# tweeq-eMod_Splitter_UART.net
KiCad netlist of a schematic drawn in EAGLE
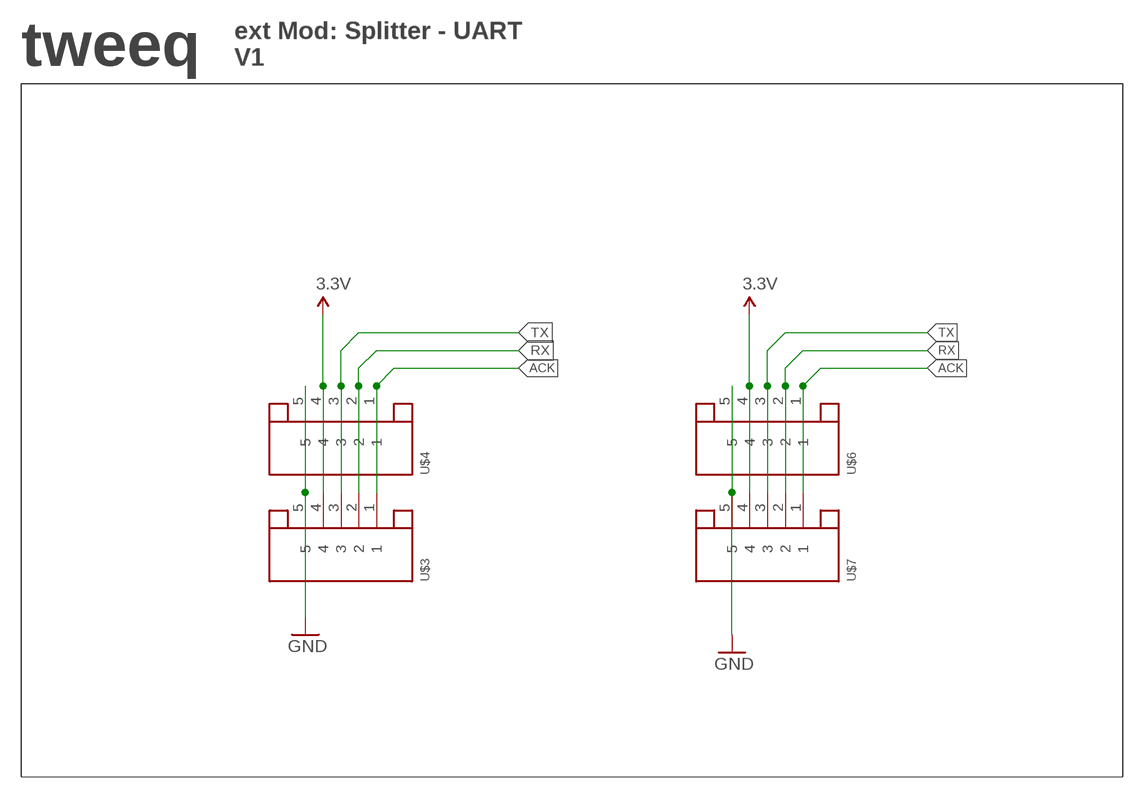
[diagram p0: schematic, sheet 1]

(export (version "E")
  (design (tool "Eeschema 10.0.6"))
  (components
    (comp (ref "U$3")
      (value "JST-5PINSH")
      (footprint "eagle-import:SH1.0-5PIN")
      (libsource (lib "eagle-import") (part "JST-5PINSH"))
    )
    (comp (ref "U$4")
      (value "JST-5PINSH")
      (footprint "eagle-import:SH1.0-5PIN")
      (libsource (lib "eagle-import") (part "JST-5PINSH"))
    )
    (comp (ref "U$6")
      (value "JST-5PINSH")
      (footprint "eagle-import:SH1.0-5PIN")
      (libsource (lib "eagle-import") (part "JST-5PINSH"))
    )
    (comp (ref "U$7")
      (value "JST-5PINSH")
      (footprint "eagle-import:SH1.0-5PIN")
      (libsource (lib "eagle-import") (part "JST-5PINSH"))
    )
  )
  (nets
    (net (code "1") (name "3.3V") (class "Default")
      (node (ref "U$3") (pin "4") (pinfunction "4_4") (pintype "bidirectional"))
      (node (ref "U$4") (pin "4") (pinfunction "4_4") (pintype "bidirectional"))
      (node (ref "U$6") (pin "4") (pinfunction "4_4") (pintype "bidirectional"))
      (node (ref "U$7") (pin "4") (pinfunction "4_4") (pintype "bidirectional"))
    )
    (net (code "2") (name "ACK") (class "Default")
      (node (ref "U$3") (pin "1") (pinfunction "1_1") (pintype "bidirectional"))
      (node (ref "U$4") (pin "1") (pinfunction "1_1") (pintype "bidirectional"))
      (node (ref "U$6") (pin "1") (pinfunction "1_1") (pintype "bidirectional"))
      (node (ref "U$7") (pin "1") (pinfunction "1_1") (pintype "bidirectional"))
    )
    (net (code "3") (name "GND") (class "Default")
      (node (ref "U$3") (pin "5") (pinfunction "5_5") (pintype "bidirectional"))
      (node (ref "U$4") (pin "5") (pinfunction "5_5") (pintype "bidirectional"))
      (node (ref "U$6") (pin "5") (pinfunction "5_5") (pintype "bidirectional"))
      (node (ref "U$7") (pin "5") (pinfunction "5_5") (pintype "bidirectional"))
    )
    (net (code "4") (name "RX") (class "Default")
      (node (ref "U$3") (pin "2") (pinfunction "2_2") (pintype "bidirectional"))
      (node (ref "U$4") (pin "2") (pinfunction "2_2") (pintype "bidirectional"))
      (node (ref "U$6") (pin "2") (pinfunction "2_2") (pintype "bidirectional"))
      (node (ref "U$7") (pin "2") (pinfunction "2_2") (pintype "bidirectional"))
    )
    (net (code "5") (name "TX") (class "Default")
      (node (ref "U$3") (pin "3") (pinfunction "3_3") (pintype "bidirectional"))
      (node (ref "U$4") (pin "3") (pinfunction "3_3") (pintype "bidirectional"))
      (node (ref "U$6") (pin "3") (pinfunction "3_3") (pintype "bidirectional"))
      (node (ref "U$7") (pin "3") (pinfunction "3_3") (pintype "bidirectional"))
    )
  )
)
